# legatus_v0_2.net
KiCad netlist of a schematic drawn in EAGLE
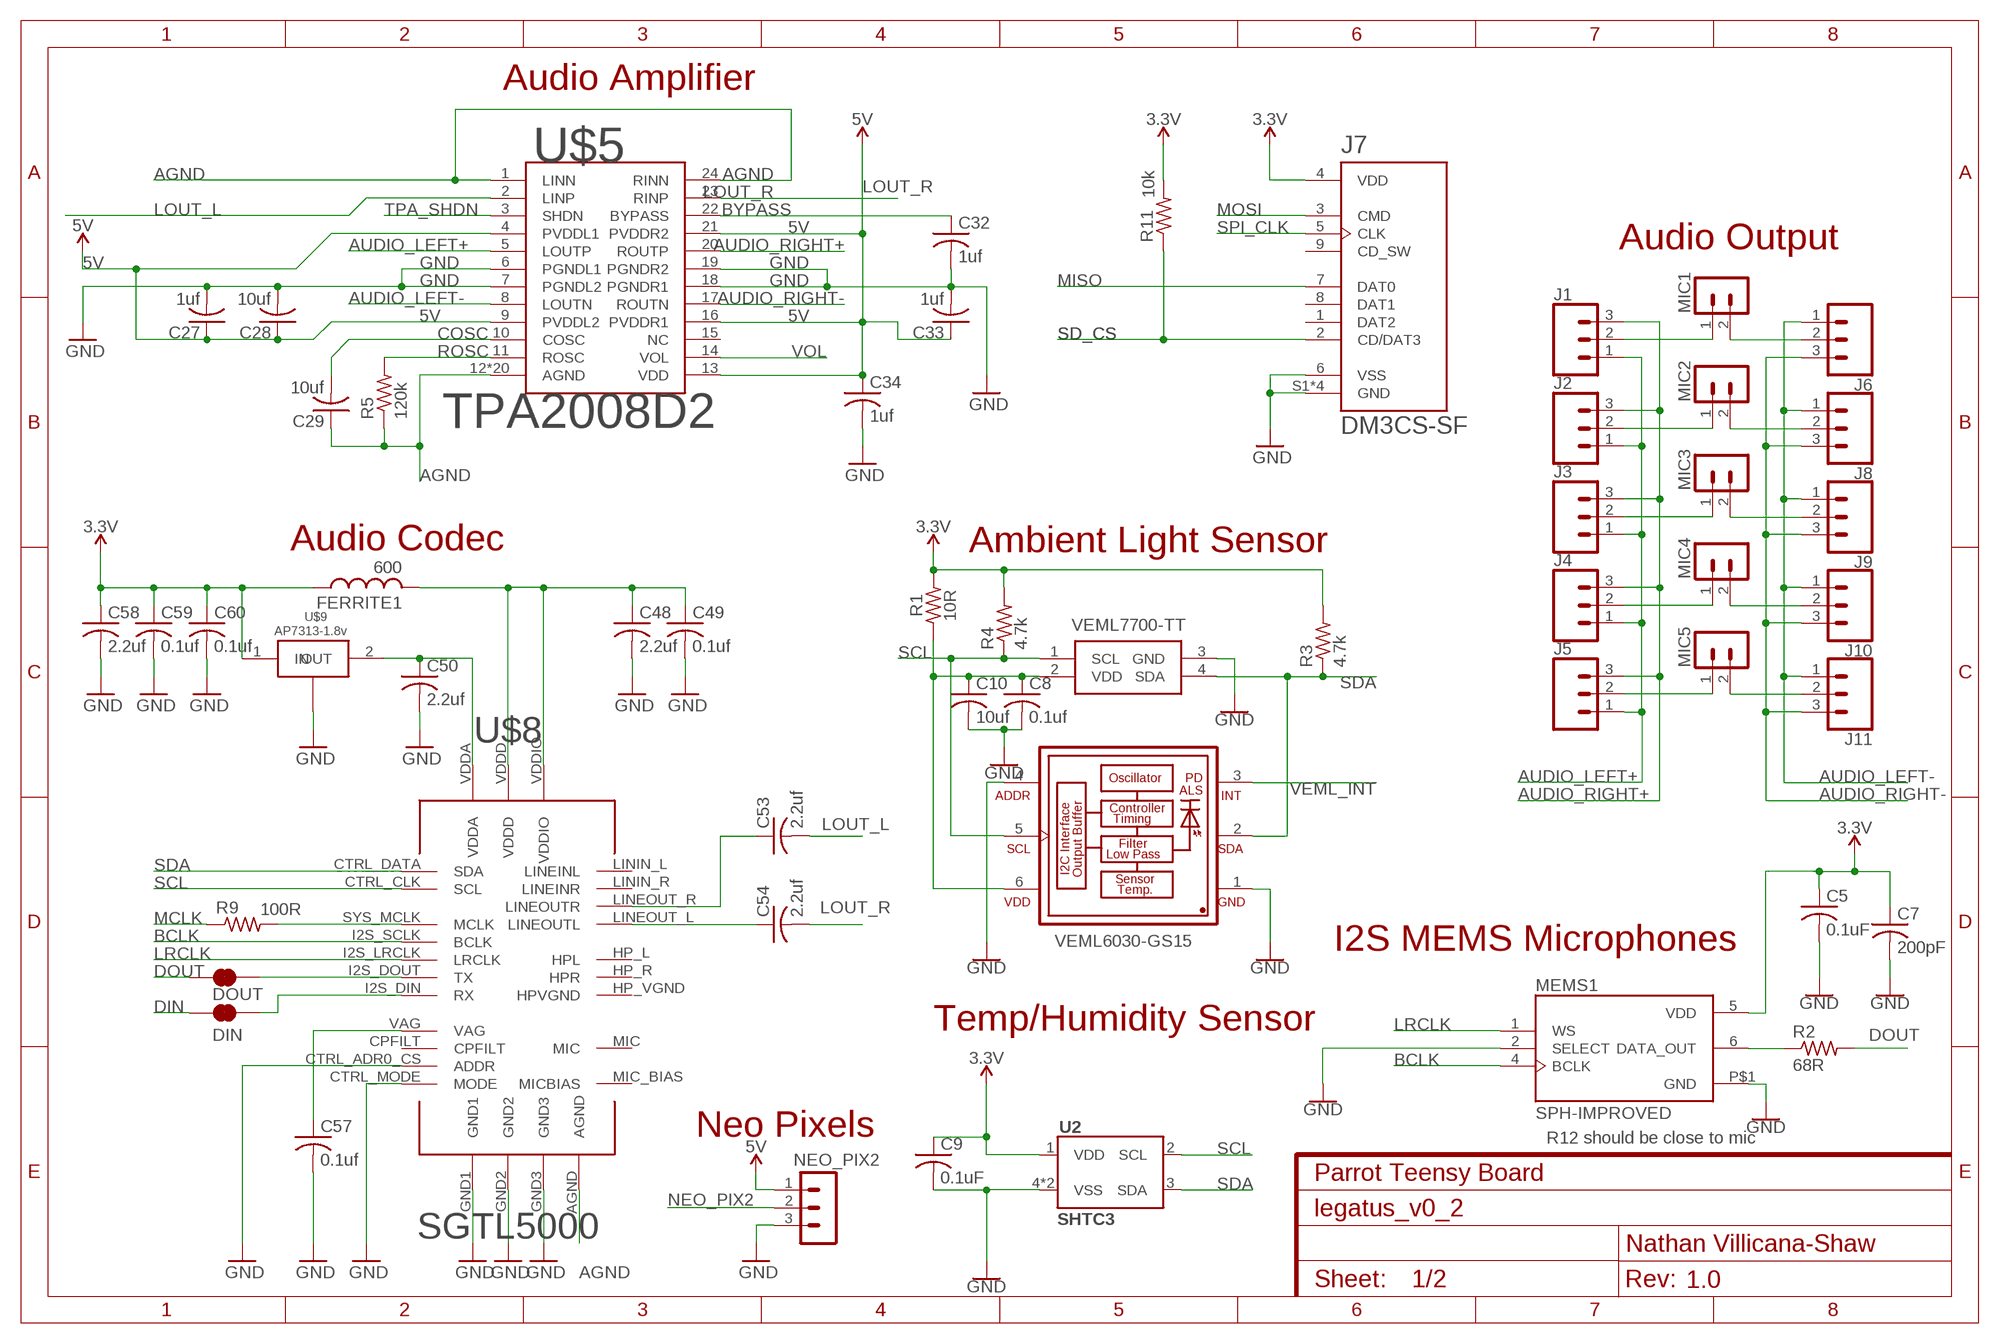
[diagram p0: schematic, sheet 1]
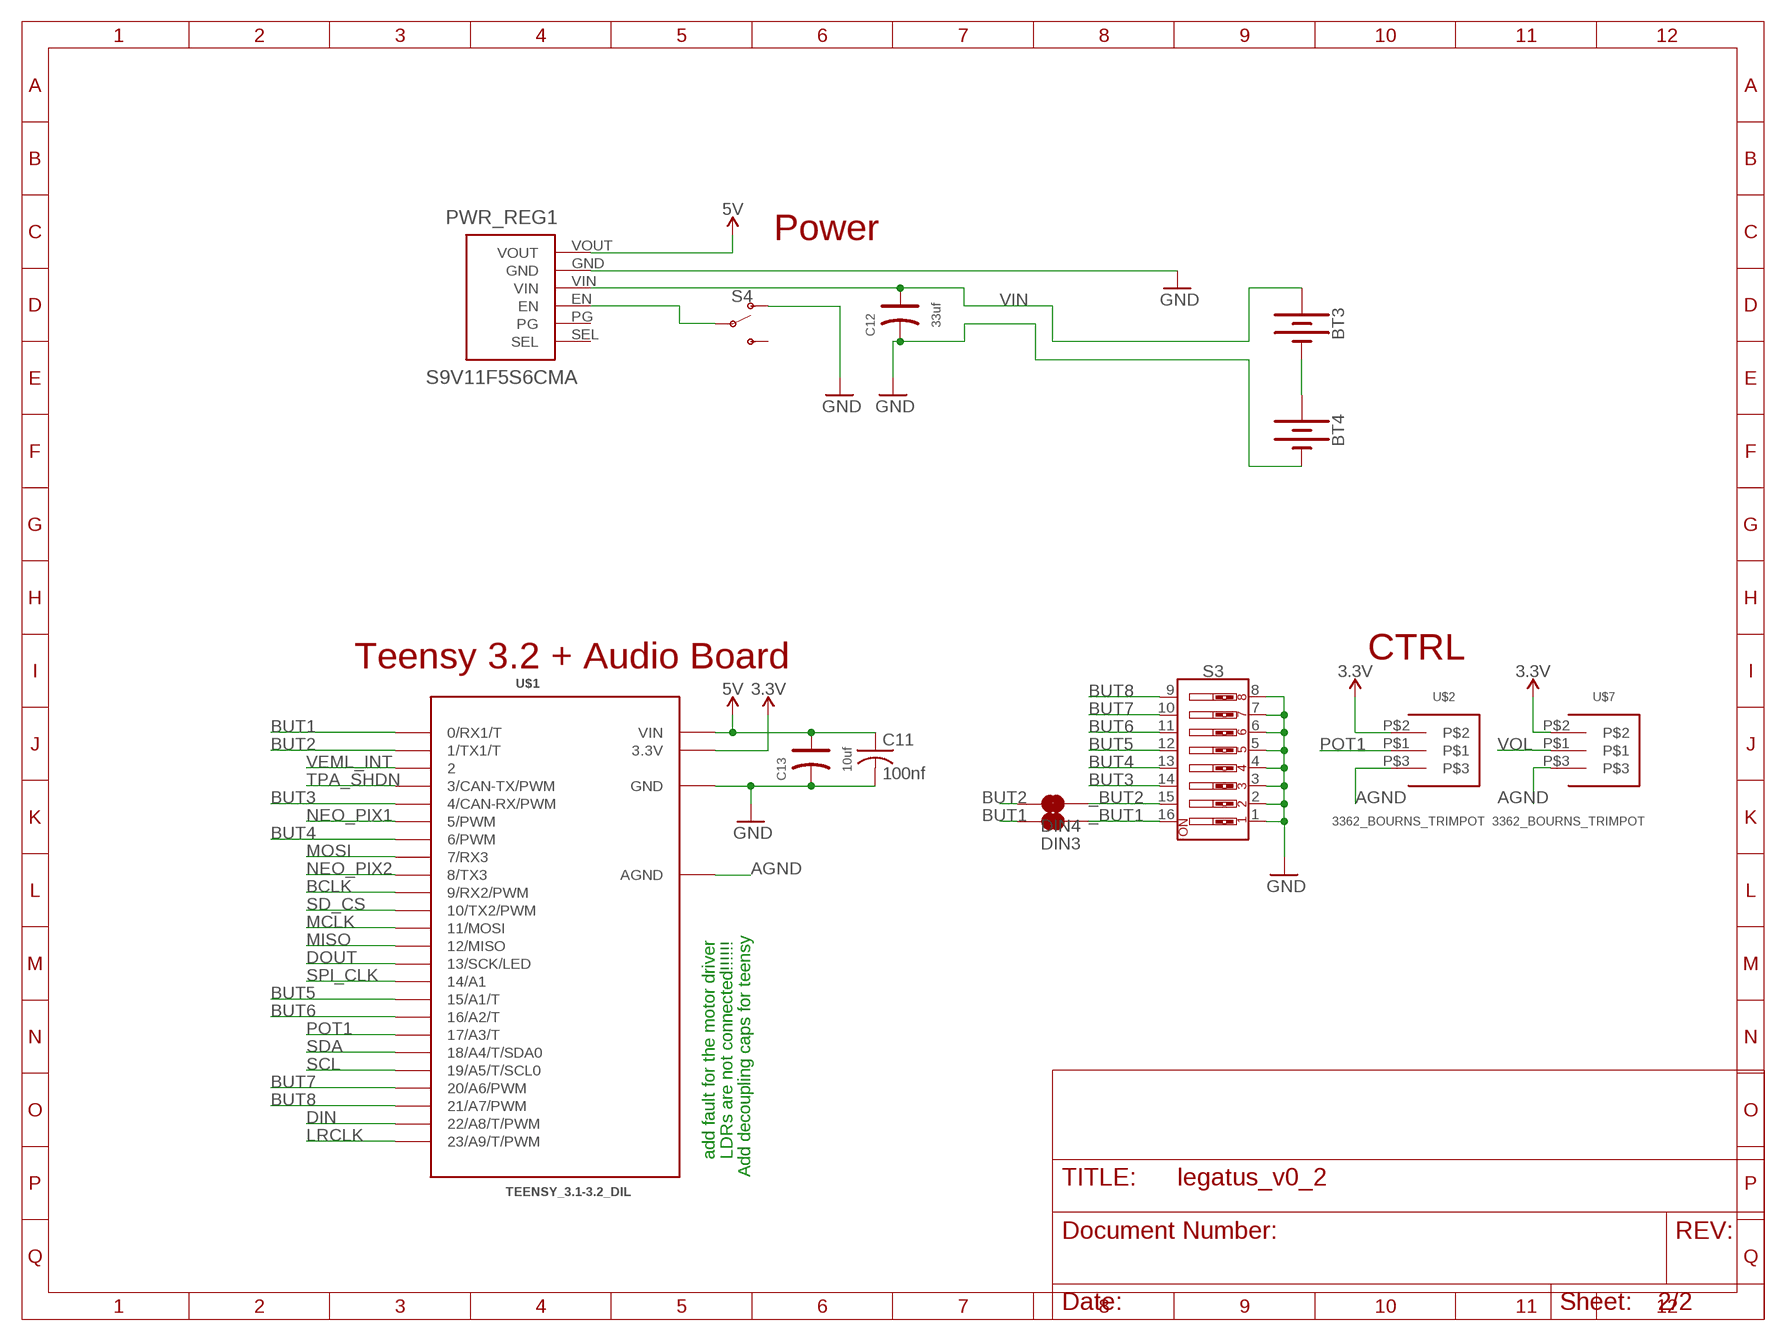
[diagram p1: schematic, sheet 2, part 1 of 2]
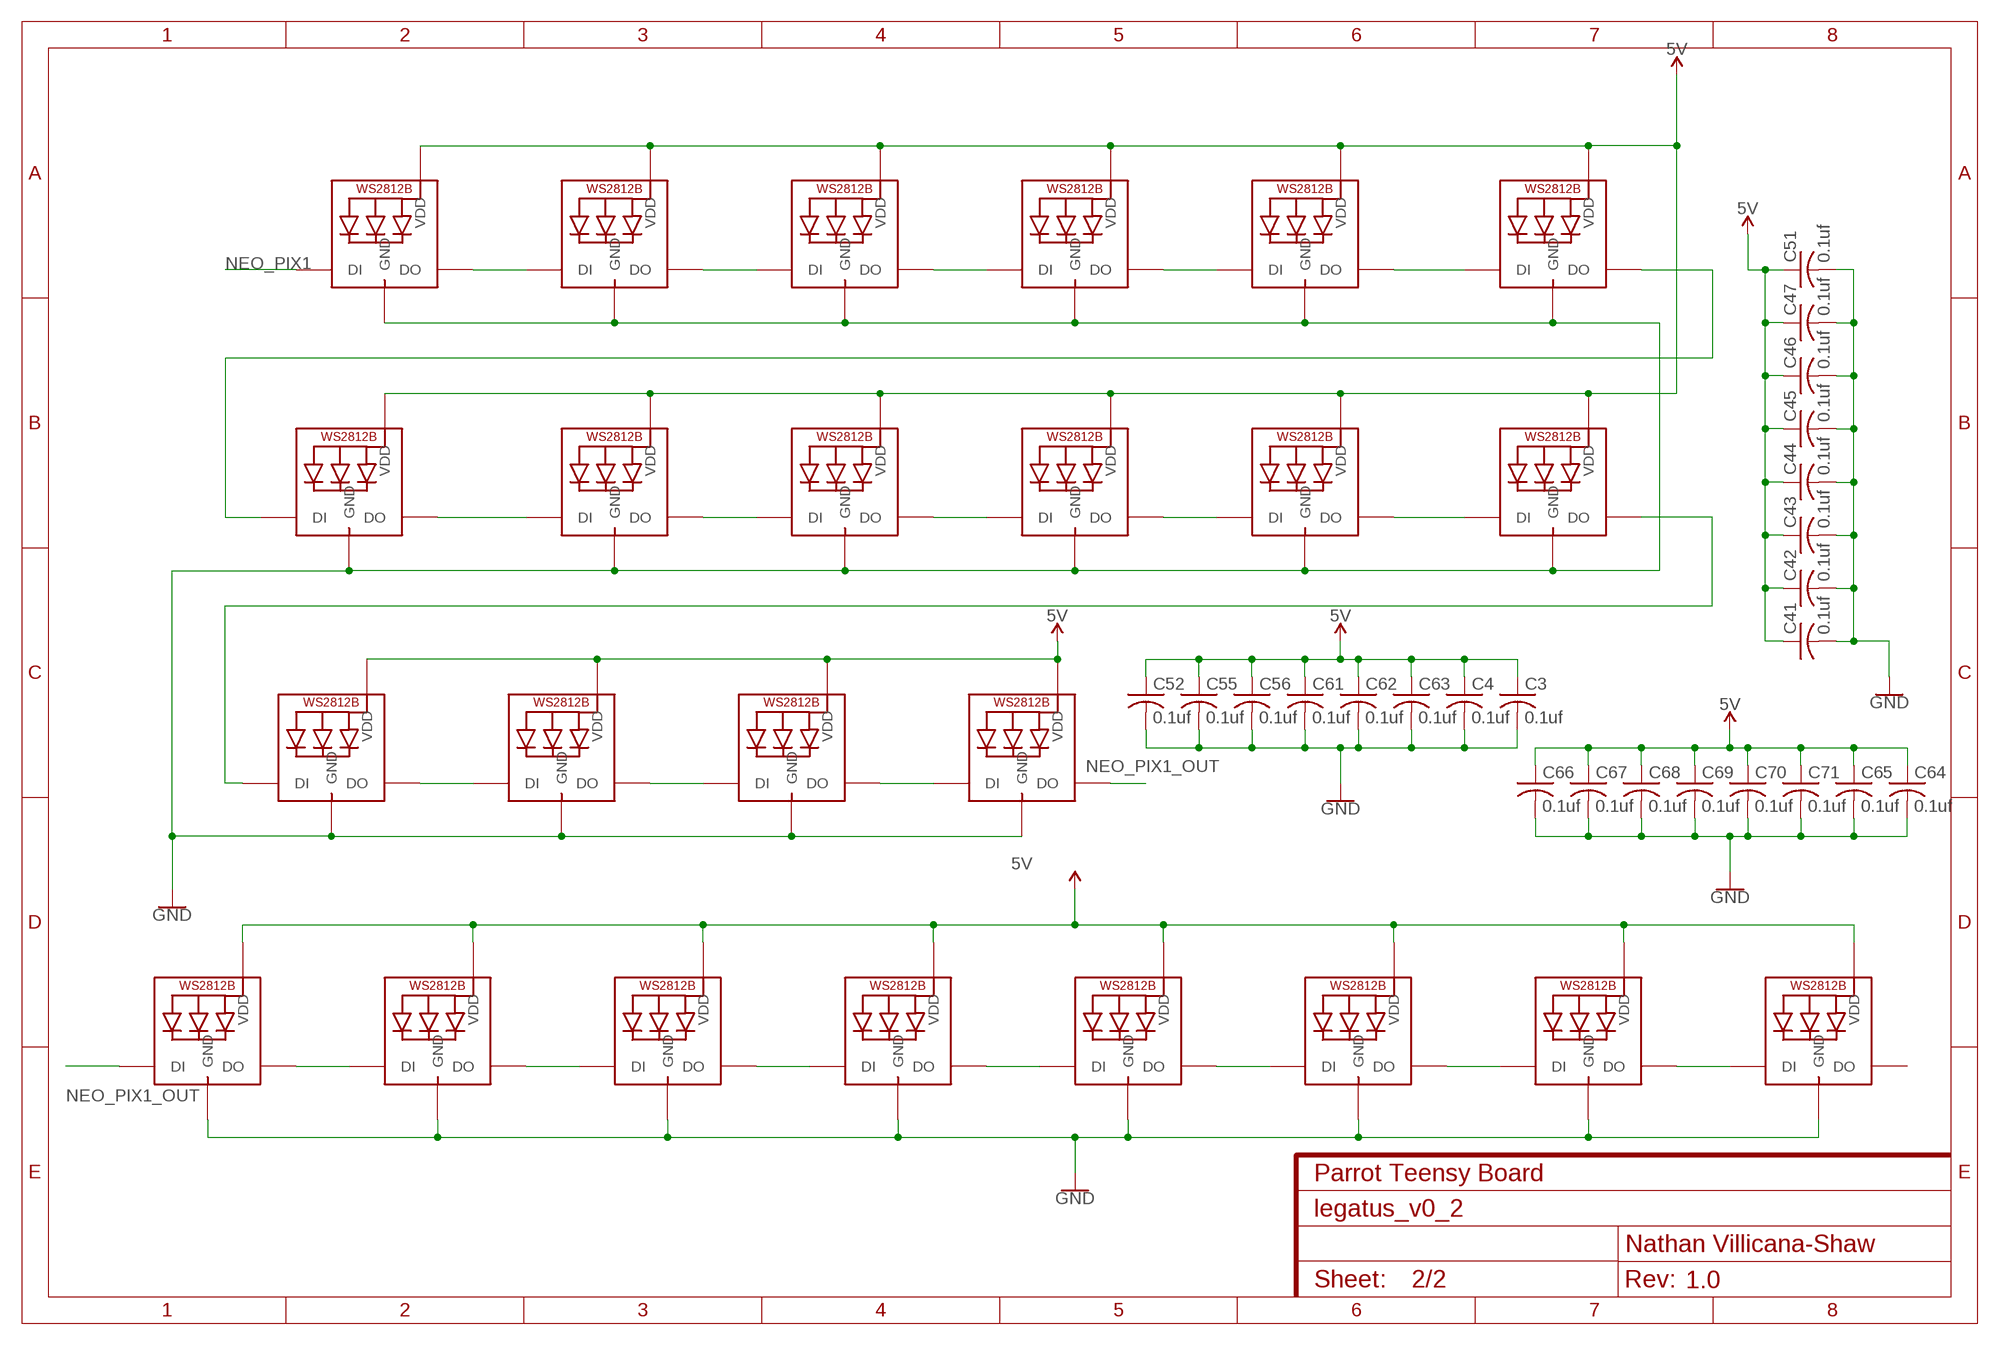
[diagram p2: schematic, sheet 2, part 2 of 2]

(export (version "E")
  (design (tool "Eeschema 10.0.6"))
  (components
    (comp (ref "C5")
      (value "0.1uF")
      (footprint "eagle-import:C0805")
      (libsource (lib "eagle-import") (part "rcl_334_C-USC0805"))
    )
    (comp (ref "C7")
      (value "200pF")
      (footprint "eagle-import:C0805")
      (libsource (lib "eagle-import") (part "rcl_334_C-USC0805"))
    )
    (comp (ref "C8")
      (value "0.1uf")
      (footprint "eagle-import:C0805")
      (libsource (lib "eagle-import") (part "rcl_334_C-USC0805"))
    )
    (comp (ref "C9")
      (value "0.1uF")
      (footprint "eagle-import:C0805")
      (libsource (lib "eagle-import") (part "rcl_334_C-USC0805"))
    )
    (comp (ref "C10")
      (value "10uf")
      (footprint "eagle-import:C0805")
      (libsource (lib "eagle-import") (part "rcl_334_C-USC0805"))
    )
    (comp (ref "C27")
      (value "1uf")
      (footprint "eagle-import:C0805")
      (libsource (lib "eagle-import") (part "rcl_334_C-USC0805"))
    )
    (comp (ref "C28")
      (value "10uf")
      (footprint "eagle-import:C0805")
      (libsource (lib "eagle-import") (part "rcl_334_C-USC0805"))
    )
    (comp (ref "C29")
      (value "10uf")
      (footprint "eagle-import:C0805")
      (libsource (lib "eagle-import") (part "rcl_334_C-USC0805"))
    )
    (comp (ref "C32")
      (value "1uf")
      (footprint "eagle-import:C0805")
      (libsource (lib "eagle-import") (part "rcl_334_C-USC0805"))
    )
    (comp (ref "C33")
      (value "1uf")
      (footprint "eagle-import:C0805")
      (libsource (lib "eagle-import") (part "rcl_334_C-USC0805"))
    )
    (comp (ref "C34")
      (value "1uf")
      (footprint "eagle-import:C0805")
      (libsource (lib "eagle-import") (part "rcl_334_C-USC0805"))
    )
    (comp (ref "C48")
      (value "2.2uf")
      (footprint "eagle-import:C0805")
      (libsource (lib "eagle-import") (part "rcl_334_C-USC0805"))
    )
    (comp (ref "C49")
      (value "0.1uf")
      (footprint "eagle-import:C0805")
      (libsource (lib "eagle-import") (part "rcl_334_C-USC0805"))
    )
    (comp (ref "C50")
      (value "2.2uf")
      (footprint "eagle-import:C0805")
      (libsource (lib "eagle-import") (part "rcl_334_C-USC0805"))
    )
    (comp (ref "C53")
      (value "2.2uf")
      (footprint "eagle-import:C0805")
      (libsource (lib "eagle-import") (part "rcl_334_C-USC0805"))
    )
    (comp (ref "C54")
      (value "2.2uf")
      (footprint "eagle-import:C0805")
      (libsource (lib "eagle-import") (part "rcl_334_C-USC0805"))
    )
    (comp (ref "C57")
      (value "0.1uf")
      (footprint "eagle-import:C0805")
      (libsource (lib "eagle-import") (part "rcl_334_C-USC0805"))
    )
    (comp (ref "C58")
      (value "2.2uf")
      (footprint "eagle-import:C0805")
      (libsource (lib "eagle-import") (part "rcl_334_C-USC0805"))
    )
    (comp (ref "C59")
      (value "0.1uf")
      (footprint "eagle-import:C0805")
      (libsource (lib "eagle-import") (part "rcl_334_C-USC0805"))
    )
    (comp (ref "C60")
      (value "0.1uf")
      (footprint "eagle-import:C0805")
      (libsource (lib "eagle-import") (part "rcl_334_C-USC0805"))
    )
    (comp (ref "DIN")
      (value "JUMPER-SMT_2_NC_TRACE_SILK")
      (footprint "eagle-import:SMT-JUMPER_2_NC_TRACE_SILK")
      (libsource (lib "eagle-import") (part "JUMPER-SMT_2_NC_TRACE_SILK"))
    )
    (comp (ref "DOUT")
      (value "JUMPER-SMT_2_NC_TRACE_SILK")
      (footprint "eagle-import:SMT-JUMPER_2_NC_TRACE_SILK")
      (libsource (lib "eagle-import") (part "JUMPER-SMT_2_NC_TRACE_SILK"))
    )
    (comp (ref "FERRITE1")
      (value "600")
      (footprint "eagle-import:RESC0805_N")
      (libsource (lib "eagle-import") (part "INDUCTOR_0805_N"))
    )
    (comp (ref "J1")
      (value "CONN_03")
      (footprint "eagle-import:1X03")
      (libsource (lib "eagle-import") (part "CONN_03"))
    )
    (comp (ref "J2")
      (value "CONN_03")
      (footprint "eagle-import:1X03")
      (libsource (lib "eagle-import") (part "CONN_03"))
    )
    (comp (ref "J3")
      (value "CONN_03")
      (footprint "eagle-import:1X03")
      (libsource (lib "eagle-import") (part "CONN_03"))
    )
    (comp (ref "J4")
      (value "CONN_03")
      (footprint "eagle-import:1X03")
      (libsource (lib "eagle-import") (part "CONN_03"))
    )
    (comp (ref "J5")
      (value "CONN_03")
      (footprint "eagle-import:1X03")
      (libsource (lib "eagle-import") (part "CONN_03"))
    )
    (comp (ref "J6")
      (value "CONN_03")
      (footprint "eagle-import:1X03")
      (libsource (lib "eagle-import") (part "CONN_03"))
    )
    (comp (ref "J7")
      (value "DM3CS-SF")
      (footprint "eagle-import:HRS_DM3CS-SF")
      (fields (field (name "MF") "Hirose"))
      (libsource (lib "eagle-import") (part "DM3CS-SF"))
    )
    (comp (ref "J8")
      (value "CONN_03")
      (footprint "eagle-import:1X03")
      (libsource (lib "eagle-import") (part "CONN_03"))
    )
    (comp (ref "J9")
      (value "CONN_03")
      (footprint "eagle-import:1X03")
      (libsource (lib "eagle-import") (part "CONN_03"))
    )
    (comp (ref "J10")
      (value "CONN_03")
      (footprint "eagle-import:1X03")
      (libsource (lib "eagle-import") (part "CONN_03"))
    )
    (comp (ref "J11")
      (value "CONN_03")
      (footprint "eagle-import:1X03")
      (libsource (lib "eagle-import") (part "CONN_03"))
    )
    (comp (ref "MEMS1")
      (value "SPH-IMPROVED")
      (footprint "eagle-import:MIC_SPH0645LM4H-B_LARGER_RING")
      (libsource (lib "eagle-import") (part "SPH-IMPROVED"))
    )
    (comp (ref "MIC1")
      (value "B2B-PH-K")
      (footprint "eagle-import:B2B-PH-K")
      (libsource (lib "eagle-import") (part "B2B-PH-K"))
    )
    (comp (ref "MIC2")
      (value "B2B-PH-K")
      (footprint "eagle-import:B2B-PH-K")
      (libsource (lib "eagle-import") (part "B2B-PH-K"))
    )
    (comp (ref "MIC3")
      (value "B2B-PH-K")
      (footprint "eagle-import:B2B-PH-K")
      (libsource (lib "eagle-import") (part "B2B-PH-K"))
    )
    (comp (ref "MIC4")
      (value "B2B-PH-K")
      (footprint "eagle-import:B2B-PH-K")
      (libsource (lib "eagle-import") (part "B2B-PH-K"))
    )
    (comp (ref "MIC5")
      (value "B2B-PH-K")
      (footprint "eagle-import:B2B-PH-K")
      (libsource (lib "eagle-import") (part "B2B-PH-K"))
    )
    (comp (ref "NEO_PIX2")
      (value "B3B-PH-K")
      (footprint "eagle-import:B3B-PH-K")
      (libsource (lib "eagle-import") (part "B3B-PH-K"))
    )
    (comp (ref "R1")
      (value "10R")
      (footprint "eagle-import:R0805")
      (libsource (lib "eagle-import") (part "audio amplifier example_970892_R-US_R0805"))
    )
    (comp (ref "R2")
      (value "68R")
      (footprint "eagle-import:M0805")
      (libsource (lib "eagle-import") (part "R-US_M0805"))
    )
    (comp (ref "R3")
      (value "4.7k")
      (footprint "eagle-import:M0805")
      (libsource (lib "eagle-import") (part "R-US_M0805"))
    )
    (comp (ref "R4")
      (value "4.7k")
      (footprint "eagle-import:M0805")
      (libsource (lib "eagle-import") (part "R-US_M0805"))
    )
    (comp (ref "R5")
      (value "120k")
      (footprint "eagle-import:M0805")
      (libsource (lib "eagle-import") (part "R-US_M0805"))
    )
    (comp (ref "R9")
      (value "100R")
      (footprint "eagle-import:M0805")
      (libsource (lib "eagle-import") (part "rcl_R-US_M0805"))
    )
    (comp (ref "R11")
      (value "10k")
      (footprint "eagle-import:M0805")
      (libsource (lib "eagle-import") (part "rcl_R-US_M0805"))
    )
    (comp (ref "U$5")
      (value "TPA2008D2")
      (footprint "eagle-import:PWP-TSSOP24")
      (libsource (lib "eagle-import") (part "TPA2008D2"))
    )
    (comp (ref "U$8")
      (value "SGTL5000")
      (footprint "eagle-import:QFN-32-5X5MM")
      (libsource (lib "eagle-import") (part "SGTL5000"))
    )
    (comp (ref "U$9")
      (value "AP7313-1.8v")
      (footprint "eagle-import:SOT-23")
      (libsource (lib "eagle-import") (part "AP7313"))
    )
    (comp (ref "U2")
      (value "SHTC3")
      (footprint "eagle-import:SHTC3")
      (libsource (lib "eagle-import") (part "SHTC3"))
    )
    (comp (ref "VEML1")
      (value "VEML7700-TT")
      (footprint "eagle-import:VEML7700")
      (fields (field (name "MOUSER_PART_NUMBER") "78-VEML7700-TT") (field (name "RS_PART_NUMBER") "1226791P"))
      (libsource (lib "eagle-import") (part "VEML7700-TT"))
    )
    (comp (ref "VMEL1")
      (value "VEML6030-GS15")
      (footprint "eagle-import:VISHAY_VEML6030_2X2X0.87")
      (fields (field (name "MF") "Vishay Semiconductor"))
      (libsource (lib "eagle-import") (part "VEML6030-GS15"))
    )
    (comp (ref "BT3")
      (value "BATTERY-18650")
      (footprint "eagle-import:BATTERY_18650-HOLDER")
      (libsource (lib "eagle-import") (part "BATTERY-18650"))
    )
    (comp (ref "BT4")
      (value "BATTERY-18650")
      (footprint "eagle-import:BATTERY_18650-HOLDER")
      (libsource (lib "eagle-import") (part "BATTERY-18650"))
    )
    (comp (ref "C3")
      (value "0.1uf")
      (footprint "eagle-import:C0805")
      (libsource (lib "eagle-import") (part "rcl_334_C-USC0805"))
    )
    (comp (ref "C4")
      (value "0.1uf")
      (footprint "eagle-import:C0805")
      (libsource (lib "eagle-import") (part "rcl_334_C-USC0805"))
    )
    (comp (ref "C11")
      (value "100nf")
      (footprint "eagle-import:C2012")
      (libsource (lib "eagle-import") (part "C-USC2012"))
    )
    (comp (ref "C12")
      (value "33uf")
      (footprint "eagle-import:PC-D5.3MM")
      (fields (field (name "MPN") "KS 100uF/16V"))
      (libsource (lib "eagle-import") (part "DIP-ALUMINUM-47UF-16V(D5-H7MM)"))
    )
    (comp (ref "C13")
      (value "10uf")
      (footprint "eagle-import:PC-D5.3MM")
      (fields (field (name "MPN") "KS 100uF/16V"))
      (libsource (lib "eagle-import") (part "DIP-ALUMINUM-47UF-16V(D5-H7MM)"))
    )
    (comp (ref "C41")
      (value "0.1uf")
      (footprint "eagle-import:C0805")
      (libsource (lib "eagle-import") (part "rcl_334_C-USC0805"))
    )
    (comp (ref "C42")
      (value "0.1uf")
      (footprint "eagle-import:C0805")
      (libsource (lib "eagle-import") (part "rcl_334_C-USC0805"))
    )
    (comp (ref "C43")
      (value "0.1uf")
      (footprint "eagle-import:C0805")
      (libsource (lib "eagle-import") (part "rcl_334_C-USC0805"))
    )
    (comp (ref "C44")
      (value "0.1uf")
      (footprint "eagle-import:C0805")
      (libsource (lib "eagle-import") (part "rcl_334_C-USC0805"))
    )
    (comp (ref "C45")
      (value "0.1uf")
      (footprint "eagle-import:C0805")
      (libsource (lib "eagle-import") (part "rcl_334_C-USC0805"))
    )
    (comp (ref "C46")
      (value "0.1uf")
      (footprint "eagle-import:C0805")
      (libsource (lib "eagle-import") (part "rcl_334_C-USC0805"))
    )
    (comp (ref "C47")
      (value "0.1uf")
      (footprint "eagle-import:C0805")
      (libsource (lib "eagle-import") (part "rcl_334_C-USC0805"))
    )
    (comp (ref "C51")
      (value "0.1uf")
      (footprint "eagle-import:C0805")
      (libsource (lib "eagle-import") (part "rcl_334_C-USC0805"))
    )
    (comp (ref "C52")
      (value "0.1uf")
      (footprint "eagle-import:C0805")
      (libsource (lib "eagle-import") (part "rcl_334_C-USC0805"))
    )
    (comp (ref "C55")
      (value "0.1uf")
      (footprint "eagle-import:C0805")
      (libsource (lib "eagle-import") (part "rcl_334_C-USC0805"))
    )
    (comp (ref "C56")
      (value "0.1uf")
      (footprint "eagle-import:C0805")
      (libsource (lib "eagle-import") (part "rcl_334_C-USC0805"))
    )
    (comp (ref "C61")
      (value "0.1uf")
      (footprint "eagle-import:C0805")
      (libsource (lib "eagle-import") (part "rcl_334_C-USC0805"))
    )
    (comp (ref "C62")
      (value "0.1uf")
      (footprint "eagle-import:C0805")
      (libsource (lib "eagle-import") (part "rcl_334_C-USC0805"))
    )
    (comp (ref "C63")
      (value "0.1uf")
      (footprint "eagle-import:C0805")
      (libsource (lib "eagle-import") (part "rcl_334_C-USC0805"))
    )
    (comp (ref "C64")
      (value "0.1uf")
      (footprint "eagle-import:C0805")
      (libsource (lib "eagle-import") (part "rcl_334_C-USC0805"))
    )
    (comp (ref "C65")
      (value "0.1uf")
      (footprint "eagle-import:C0805")
      (libsource (lib "eagle-import") (part "rcl_334_C-USC0805"))
    )
    (comp (ref "C66")
      (value "0.1uf")
      (footprint "eagle-import:C0805")
      (libsource (lib "eagle-import") (part "rcl_334_C-USC0805"))
    )
    (comp (ref "C67")
      (value "0.1uf")
      (footprint "eagle-import:C0805")
      (libsource (lib "eagle-import") (part "rcl_334_C-USC0805"))
    )
    (comp (ref "C68")
      (value "0.1uf")
      (footprint "eagle-import:C0805")
      (libsource (lib "eagle-import") (part "rcl_334_C-USC0805"))
    )
    (comp (ref "C69")
      (value "0.1uf")
      (footprint "eagle-import:C0805")
      (libsource (lib "eagle-import") (part "rcl_334_C-USC0805"))
    )
    (comp (ref "C70")
      (value "0.1uf")
      (footprint "eagle-import:C0805")
      (libsource (lib "eagle-import") (part "rcl_334_C-USC0805"))
    )
    (comp (ref "C71")
      (value "0.1uf")
      (footprint "eagle-import:C0805")
      (libsource (lib "eagle-import") (part "rcl_334_C-USC0805"))
    )
    (comp (ref "DIN3")
      (value "JUMPER-SMT_2_NC_TRACE_SILK")
      (footprint "eagle-import:SMT-JUMPER_2_NC_TRACE_SILK")
      (libsource (lib "eagle-import") (part "JUMPER-SMT_2_NC_TRACE_SILK"))
    )
    (comp (ref "DIN4")
      (value "JUMPER-SMT_2_NC_TRACE_SILK")
      (footprint "eagle-import:SMT-JUMPER_2_NC_TRACE_SILK")
      (libsource (lib "eagle-import") (part "JUMPER-SMT_2_NC_TRACE_SILK"))
    )
    (comp (ref "LED25")
      (value "WS2812B_5050N")
      (footprint "eagle-import:WS2812B-NARROW")
      (libsource (lib "eagle-import") (part "WS2812B_5050N"))
    )
    (comp (ref "LED26")
      (value "WS2812B_5050N")
      (footprint "eagle-import:WS2812B-NARROW")
      (libsource (lib "eagle-import") (part "WS2812B_5050N"))
    )
    (comp (ref "LED27")
      (value "WS2812B_5050N")
      (footprint "eagle-import:WS2812B-NARROW")
      (libsource (lib "eagle-import") (part "WS2812B_5050N"))
    )
    (comp (ref "LED28")
      (value "WS2812B_5050N")
      (footprint "eagle-import:WS2812B-NARROW")
      (libsource (lib "eagle-import") (part "WS2812B_5050N"))
    )
    (comp (ref "LED29")
      (value "WS2812B_5050N")
      (footprint "eagle-import:WS2812B-NARROW")
      (libsource (lib "eagle-import") (part "WS2812B_5050N"))
    )
    (comp (ref "LED30")
      (value "WS2812B_5050N")
      (footprint "eagle-import:WS2812B-NARROW")
      (libsource (lib "eagle-import") (part "WS2812B_5050N"))
    )
    (comp (ref "LED31")
      (value "WS2812B_5050N")
      (footprint "eagle-import:WS2812B-NARROW")
      (libsource (lib "eagle-import") (part "WS2812B_5050N"))
    )
    (comp (ref "LED32")
      (value "WS2812B_5050N")
      (footprint "eagle-import:WS2812B-NARROW")
      (libsource (lib "eagle-import") (part "WS2812B_5050N"))
    )
    (comp (ref "LED33")
      (value "WS2812B_5050N")
      (footprint "eagle-import:WS2812B-NARROW")
      (libsource (lib "eagle-import") (part "WS2812B_5050N"))
    )
    (comp (ref "LED34")
      (value "WS2812B_5050N")
      (footprint "eagle-import:WS2812B-NARROW")
      (libsource (lib "eagle-import") (part "WS2812B_5050N"))
    )
    (comp (ref "LED35")
      (value "WS2812B_5050N")
      (footprint "eagle-import:WS2812B-NARROW")
      (libsource (lib "eagle-import") (part "WS2812B_5050N"))
    )
    (comp (ref "LED36")
      (value "WS2812B_5050N")
      (footprint "eagle-import:WS2812B-NARROW")
      (libsource (lib "eagle-import") (part "WS2812B_5050N"))
    )
    (comp (ref "LED37")
      (value "WS2812B_5050N")
      (footprint "eagle-import:WS2812B-NARROW")
      (libsource (lib "eagle-import") (part "WS2812B_5050N"))
    )
    (comp (ref "LED38")
      (value "WS2812B_5050N")
      (footprint "eagle-import:WS2812B-NARROW")
      (libsource (lib "eagle-import") (part "WS2812B_5050N"))
    )
    (comp (ref "LED39")
      (value "WS2812B_5050N")
      (footprint "eagle-import:WS2812B-NARROW")
      (libsource (lib "eagle-import") (part "WS2812B_5050N"))
    )
    (comp (ref "LED40")
      (value "WS2812B_5050N")
      (footprint "eagle-import:WS2812B-NARROW")
      (libsource (lib "eagle-import") (part "WS2812B_5050N"))
    )
    (comp (ref "LED41")
      (value "WS2812B_5050N")
      (footprint "eagle-import:WS2812B-NARROW")
      (libsource (lib "eagle-import") (part "WS2812B_5050N"))
    )
    (comp (ref "LED42")
      (value "WS2812B_5050N")
      (footprint "eagle-import:WS2812B-NARROW")
      (libsource (lib "eagle-import") (part "WS2812B_5050N"))
    )
    (comp (ref "LED43")
      (value "WS2812B_5050N")
      (footprint "eagle-import:WS2812B-NARROW")
      (libsource (lib "eagle-import") (part "WS2812B_5050N"))
    )
    (comp (ref "LED44")
      (value "WS2812B_5050N")
      (footprint "eagle-import:WS2812B-NARROW")
      (libsource (lib "eagle-import") (part "WS2812B_5050N"))
    )
    (comp (ref "LED45")
      (value "WS2812B_5050N")
      (footprint "eagle-import:WS2812B-NARROW")
      (libsource (lib "eagle-import") (part "WS2812B_5050N"))
    )
    (comp (ref "LED46")
      (value "WS2812B_5050N")
      (footprint "eagle-import:WS2812B-NARROW")
      (libsource (lib "eagle-import") (part "WS2812B_5050N"))
    )
    (comp (ref "LED47")
      (value "WS2812B_5050N")
      (footprint "eagle-import:WS2812B-NARROW")
      (libsource (lib "eagle-import") (part "WS2812B_5050N"))
    )
    (comp (ref "LED48")
      (value "WS2812B_5050N")
      (footprint "eagle-import:WS2812B-NARROW")
      (libsource (lib "eagle-import") (part "WS2812B_5050N"))
    )
    (comp (ref "PWR_REG1")
      (value "S9V11F5S6CMA")
      (footprint "eagle-import:S9V11F3S5CMA")
      (libsource (lib "eagle-import") (part "S9V11F5S6CMA"))
    )
    (comp (ref "S3")
      (value "DIP-08-PTH")
      (footprint "eagle-import:DIPSWITCH-08")
      (libsource (lib "eagle-import") (part "DIP-08-PTH"))
    )
    (comp (ref "S4")
      (value "SWITCH-SPDT-PTH-11.6X4.0MM-LOCK")
      (footprint "eagle-import:SWITCH_SPDT_PTH_11.6X4.0MM_LOCK")
      (libsource (lib "eagle-import") (part "SWITCH-SPDT-PTH-11.6X4.0MM-LOCK"))
    )
    (comp (ref "U$1")
      (value "TEENSY_3.1-3.2_DIL")
      (footprint "eagle-import:TEENSY_3.0-3.2&LC_DIL")
      (libsource (lib "eagle-import") (part "TEENSY_3.1-3.2_DIL"))
    )
    (comp (ref "U$2")
      (value "3362_BOURNS_TRIMPOT")
      (footprint "eagle-import:3362_BOURNS_TRIMPOT")
      (libsource (lib "eagle-import") (part "3362_BOURNS_TRIMPOT"))
    )
    (comp (ref "U$7")
      (value "3362_BOURNS_TRIMPOT")
      (footprint "eagle-import:3362_BOURNS_TRIMPOT")
      (libsource (lib "eagle-import") (part "3362_BOURNS_TRIMPOT"))
    )
  )
  (nets
    (net (code "1") (name "3.3V") (class "Default")
      (node (ref "C5") (pin "1") (pinfunction "1_1") (pintype "passive"))
      (node (ref "C58") (pin "1") (pinfunction "1_1") (pintype "passive"))
      (node (ref "C59") (pin "1") (pinfunction "1_1") (pintype "passive"))
      (node (ref "C60") (pin "1") (pinfunction "1_1") (pintype "passive"))
      (node (ref "C7") (pin "1") (pinfunction "1_1") (pintype "passive"))
      (node (ref "C9") (pin "1") (pinfunction "1_1") (pintype "passive"))
      (node (ref "FERRITE1") (pin "1") (pinfunction "1_1") (pintype "passive"))
      (node (ref "J7") (pin "4") (pinfunction "VDD_4") (pintype "passive"))
      (node (ref "MEMS1") (pin "5") (pinfunction "VDD_5") (pintype "power_in"))
      (node (ref "R1") (pin "2") (pinfunction "2_2") (pintype "passive"))
      (node (ref "R11") (pin "2") (pinfunction "2_2") (pintype "passive"))
      (node (ref "R3") (pin "2") (pinfunction "2_2") (pintype "passive"))
      (node (ref "R4") (pin "2") (pinfunction "2_2") (pintype "passive"))
      (node (ref "U$1") (pin "3.3V") (pinfunction "3.3V_3.3V") (pintype "power_in"))
      (node (ref "U$2") (pin "P$2") (pinfunction "P$2_P$2") (pintype "bidirectional"))
      (node (ref "U$7") (pin "P$2") (pinfunction "P$2_P$2") (pintype "bidirectional"))
      (node (ref "U$9") (pin "1") (pinfunction "IN_1") (pintype "bidirectional"))
      (node (ref "U2") (pin "1") (pinfunction "VDD_1") (pintype "bidirectional"))
    )
    (net (code "2") (name "5V") (class "Default")
      (node (ref "C11") (pin "1") (pinfunction "1_1") (pintype "passive"))
      (node (ref "C13") (pin "+") (pinfunction "+_+") (pintype "passive"))
      (node (ref "C27") (pin "1") (pinfunction "1_1") (pintype "passive"))
      (node (ref "C28") (pin "1") (pinfunction "1_1") (pintype "passive"))
      (node (ref "C3") (pin "1") (pinfunction "1_1") (pintype "passive"))
      (node (ref "C33") (pin "1") (pinfunction "1_1") (pintype "passive"))
      (node (ref "C34") (pin "1") (pinfunction "1_1") (pintype "passive"))
      (node (ref "C4") (pin "1") (pinfunction "1_1") (pintype "passive"))
      (node (ref "C41") (pin "1") (pinfunction "1_1") (pintype "passive"))
      (node (ref "C42") (pin "1") (pinfunction "1_1") (pintype "passive"))
      (node (ref "C43") (pin "1") (pinfunction "1_1") (pintype "passive"))
      (node (ref "C44") (pin "1") (pinfunction "1_1") (pintype "passive"))
      (node (ref "C45") (pin "1") (pinfunction "1_1") (pintype "passive"))
      (node (ref "C46") (pin "1") (pinfunction "1_1") (pintype "passive"))
      (node (ref "C47") (pin "1") (pinfunction "1_1") (pintype "passive"))
      (node (ref "C51") (pin "1") (pinfunction "1_1") (pintype "passive"))
      (node (ref "C52") (pin "1") (pinfunction "1_1") (pintype "passive"))
      (node (ref "C55") (pin "1") (pinfunction "1_1") (pintype "passive"))
      (node (ref "C56") (pin "1") (pinfunction "1_1") (pintype "passive"))
      (node (ref "C61") (pin "1") (pinfunction "1_1") (pintype "passive"))
      (node (ref "C62") (pin "1") (pinfunction "1_1") (pintype "passive"))
      (node (ref "C63") (pin "1") (pinfunction "1_1") (pintype "passive"))
      (node (ref "C64") (pin "1") (pinfunction "1_1") (pintype "passive"))
      (node (ref "C65") (pin "1") (pinfunction "1_1") (pintype "passive"))
      (node (ref "C66") (pin "1") (pinfunction "1_1") (pintype "passive"))
      (node (ref "C67") (pin "1") (pinfunction "1_1") (pintype "passive"))
      (node (ref "C68") (pin "1") (pinfunction "1_1") (pintype "passive"))
      (node (ref "C69") (pin "1") (pinfunction "1_1") (pintype "passive"))
      (node (ref "C70") (pin "1") (pinfunction "1_1") (pintype "passive"))
      (node (ref "C71") (pin "1") (pinfunction "1_1") (pintype "passive"))
      (node (ref "LED25") (pin "1-VDD") (pinfunction "VDD_1-VDD") (pintype "power_in"))
      (node (ref "LED26") (pin "1-VDD") (pinfunction "VDD_1-VDD") (pintype "power_in"))
      (node (ref "LED27") (pin "1-VDD") (pinfunction "VDD_1-VDD") (pintype "power_in"))
      (node (ref "LED28") (pin "1-VDD") (pinfunction "VDD_1-VDD") (pintype "power_in"))
      (node (ref "LED29") (pin "1-VDD") (pinfunction "VDD_1-VDD") (pintype "power_in"))
      (node (ref "LED30") (pin "1-VDD") (pinfunction "VDD_1-VDD") (pintype "power_in"))
      (node (ref "LED31") (pin "1-VDD") (pinfunction "VDD_1-VDD") (pintype "power_in"))
      (node (ref "LED32") (pin "1-VDD") (pinfunction "VDD_1-VDD") (pintype "power_in"))
      (node (ref "LED33") (pin "1-VDD") (pinfunction "VDD_1-VDD") (pintype "power_in"))
      (node (ref "LED34") (pin "1-VDD") (pinfunction "VDD_1-VDD") (pintype "power_in"))
      (node (ref "LED35") (pin "1-VDD") (pinfunction "VDD_1-VDD") (pintype "power_in"))
      (node (ref "LED36") (pin "1-VDD") (pinfunction "VDD_1-VDD") (pintype "power_in"))
      (node (ref "LED37") (pin "1-VDD") (pinfunction "VDD_1-VDD") (pintype "power_in"))
      (node (ref "LED38") (pin "1-VDD") (pinfunction "VDD_1-VDD") (pintype "power_in"))
      (node (ref "LED39") (pin "1-VDD") (pinfunction "VDD_1-VDD") (pintype "power_in"))
      (node (ref "LED40") (pin "1-VDD") (pinfunction "VDD_1-VDD") (pintype "power_in"))
      (node (ref "LED41") (pin "1-VDD") (pinfunction "VDD_1-VDD") (pintype "power_in"))
      (node (ref "LED42") (pin "1-VDD") (pinfunction "VDD_1-VDD") (pintype "power_in"))
      (node (ref "LED43") (pin "1-VDD") (pinfunction "VDD_1-VDD") (pintype "power_in"))
      (node (ref "LED44") (pin "1-VDD") (pinfunction "VDD_1-VDD") (pintype "power_in"))
      (node (ref "LED45") (pin "1-VDD") (pinfunction "VDD_1-VDD") (pintype "power_in"))
      (node (ref "LED46") (pin "1-VDD") (pinfunction "VDD_1-VDD") (pintype "power_in"))
      (node (ref "LED47") (pin "1-VDD") (pinfunction "VDD_1-VDD") (pintype "power_in"))
      (node (ref "LED48") (pin "1-VDD") (pinfunction "VDD_1-VDD") (pintype "power_in"))
      (node (ref "NEO_PIX2") (pin "1") (pinfunction "1_1") (pintype "passive"))
      (node (ref "PWR_REG1") (pin "VOUT") (pinfunction "VOUT_VOUT") (pintype "bidirectional"))
      (node (ref "U$1") (pin "VIN") (pinfunction "VIN_VIN") (pintype "power_in"))
      (node (ref "U$5") (pin "13") (pinfunction "VDD_13") (pintype "bidirectional"))
      (node (ref "U$5") (pin "16") (pinfunction "PVDDR1_16") (pintype "bidirectional"))
      (node (ref "U$5") (pin "21") (pinfunction "PVDDR2_21") (pintype "bidirectional"))
      (node (ref "U$5") (pin "4") (pinfunction "PVDDL1_4") (pintype "bidirectional"))
      (node (ref "U$5") (pin "9") (pinfunction "PVDDL2_9") (pintype "bidirectional"))
    )
    (net (code "3") (name "AGND") (class "Default")
      (node (ref "C29") (pin "1") (pinfunction "1_1") (pintype "passive"))
      (node (ref "R5") (pin "1") (pinfunction "1_1") (pintype "passive"))
      (node (ref "U$1") (pin "AGND") (pinfunction "AGND_AGND") (pintype "power_in"))
      (node (ref "U$2") (pin "P$3") (pinfunction "P$3_P$3") (pintype "bidirectional"))
      (node (ref "U$5") (pin "1") (pinfunction "LINN_1") (pintype "bidirectional"))
      (node (ref "U$5") (pin "12") (pinfunction "AGND_12") (pintype "bidirectional"))
      (node (ref "U$5") (pin "24") (pinfunction "RINN_24") (pintype "bidirectional"))
      (node (ref "U$5") (pin "EXP") (pinfunction "AGND_EXP") (pintype "bidirectional"))
      (node (ref "U$5") (pin "EXP@1") (pinfunction "AGND_EXP@1") (pintype "bidirectional"))
      (node (ref "U$5") (pin "EXP@10") (pinfunction "AGND_EXP@10") (pintype "bidirectional"))
      (node (ref "U$5") (pin "EXP@11") (pinfunction "AGND_EXP@11") (pintype "bidirectional"))
      (node (ref "U$5") (pin "EXP@12") (pinfunction "AGND_EXP@12") (pintype "bidirectional"))
      (node (ref "U$5") (pin "EXP@13") (pinfunction "AGND_EXP@13") (pintype "bidirectional"))
      (node (ref "U$5") (pin "EXP@14") (pinfunction "AGND_EXP@14") (pintype "bidirectional"))
      (node (ref "U$5") (pin "EXP@15") (pinfunction "AGND_EXP@15") (pintype "bidirectional"))
      (node (ref "U$5") (pin "EXP@16") (pinfunction "AGND_EXP@16") (pintype "bidirectional"))
      (node (ref "U$5") (pin "EXP@17") (pinfunction "AGND_EXP@17") (pintype "bidirectional"))
      (node (ref "U$5") (pin "EXP@18") (pinfunction "AGND_EXP@18") (pintype "bidirectional"))
      (node (ref "U$5") (pin "EXP@2") (pinfunction "AGND_EXP@2") (pintype "bidirectional"))
      (node (ref "U$5") (pin "EXP@3") (pinfunction "AGND_EXP@3") (pintype "bidirectional"))
      (node (ref "U$5") (pin "EXP@4") (pinfunction "AGND_EXP@4") (pintype "bidirectional"))
      (node (ref "U$5") (pin "EXP@5") (pinfunction "AGND_EXP@5") (pintype "bidirectional"))
      (node (ref "U$5") (pin "EXP@6") (pinfunction "AGND_EXP@6") (pintype "bidirectional"))
      (node (ref "U$5") (pin "EXP@7") (pinfunction "AGND_EXP@7") (pintype "bidirectional"))
      (node (ref "U$5") (pin "EXP@8") (pinfunction "AGND_EXP@8") (pintype "bidirectional"))
      (node (ref "U$5") (pin "EXP@9") (pinfunction "AGND_EXP@9") (pintype "bidirectional"))
      (node (ref "U$7") (pin "P$3") (pinfunction "P$3_P$3") (pintype "bidirectional"))
      (node (ref "U$8") (pin "AGND") (pinfunction "AGND_AGND") (pintype "bidirectional"))
    )
    (net (code "4") (name "AUDIO_LEFT+") (class "Default")
      (node (ref "J1") (pin "1") (pinfunction "1_1") (pintype "passive"))
      (node (ref "J2") (pin "1") (pinfunction "1_1") (pintype "passive"))
      (node (ref "J3") (pin "1") (pinfunction "1_1") (pintype "passive"))
      (node (ref "J4") (pin "1") (pinfunction "1_1") (pintype "passive"))
      (node (ref "J5") (pin "1") (pinfunction "1_1") (pintype "passive"))
      (node (ref "U$5") (pin "5") (pinfunction "LOUTP_5") (pintype "bidirectional"))
    )
    (net (code "5") (name "AUDIO_LEFT-") (class "Default")
      (node (ref "J10") (pin "1") (pinfunction "1_1") (pintype "passive"))
      (node (ref "J11") (pin "1") (pinfunction "1_1") (pintype "passive"))
      (node (ref "J6") (pin "1") (pinfunction "1_1") (pintype "passive"))
      (node (ref "J8") (pin "1") (pinfunction "1_1") (pintype "passive"))
      (node (ref "J9") (pin "1") (pinfunction "1_1") (pintype "passive"))
      (node (ref "U$5") (pin "8") (pinfunction "LOUTN_8") (pintype "bidirectional"))
    )
    (net (code "6") (name "AUDIO_RIGHT+") (class "Default")
      (node (ref "J1") (pin "3") (pinfunction "3_3") (pintype "passive"))
      (node (ref "J2") (pin "3") (pinfunction "3_3") (pintype "passive"))
      (node (ref "J3") (pin "3") (pinfunction "3_3") (pintype "passive"))
      (node (ref "J4") (pin "3") (pinfunction "3_3") (pintype "passive"))
      (node (ref "J5") (pin "3") (pinfunction "3_3") (pintype "passive"))
      (node (ref "U$5") (pin "20") (pinfunction "ROUTP_20") (pintype "bidirectional"))
    )
    (net (code "7") (name "AUDIO_RIGHT-") (class "Default")
      (node (ref "J10") (pin "3") (pinfunction "3_3") (pintype "passive"))
      (node (ref "J11") (pin "3") (pinfunction "3_3") (pintype "passive"))
      (node (ref "J6") (pin "3") (pinfunction "3_3") (pintype "passive"))
      (node (ref "J8") (pin "3") (pinfunction "3_3") (pintype "passive"))
      (node (ref "J9") (pin "3") (pinfunction "3_3") (pintype "passive"))
      (node (ref "U$5") (pin "17") (pinfunction "ROUTN_17") (pintype "bidirectional"))
    )
    (net (code "8") (name "BCLK") (class "Default")
      (node (ref "MEMS1") (pin "4") (pinfunction "BCLK_4") (pintype "input"))
      (node (ref "U$1") (pin "9") (pinfunction "9/RX2/PWM_9") (pintype "bidirectional"))
      (node (ref "U$8") (pin "I2S_SCLK") (pinfunction "BCLK_I2S_SCLK") (pintype "bidirectional"))
    )
    (net (code "9") (name "BUT1") (class "Default")
      (node (ref "DIN3") (pin "1") (pinfunction "1_1") (pintype "passive"))
      (node (ref "U$1") (pin "0") (pinfunction "0/RX1/T_0") (pintype "bidirectional"))
    )
    (net (code "10") (name "BUT2") (class "Default")
      (node (ref "DIN4") (pin "1") (pinfunction "1_1") (pintype "passive"))
      (node (ref "U$1") (pin "1") (pinfunction "1/TX1/T_1") (pintype "bidirectional"))
    )
    (net (code "11") (name "BUT3") (class "Default")
      (node (ref "S3") (pin "14") (pinfunction "14_14") (pintype "passive"))
      (node (ref "U$1") (pin "4") (pinfunction "4/CAN-RX/PWM_4") (pintype "bidirectional"))
    )
    (net (code "12") (name "BUT4") (class "Default")
      (node (ref "S3") (pin "13") (pinfunction "13_13") (pintype "passive"))
      (node (ref "U$1") (pin "6") (pinfunction "6/PWM_6") (pintype "bidirectional"))
    )
    (net (code "13") (name "BUT5") (class "Default")
      (node (ref "S3") (pin "12") (pinfunction "12_12") (pintype "passive"))
      (node (ref "U$1") (pin "15/A1") (pinfunction "15/A1/T_15/A1") (pintype "bidirectional"))
    )
    (net (code "14") (name "BUT6") (class "Default")
      (node (ref "S3") (pin "11") (pinfunction "11_11") (pintype "passive"))
      (node (ref "U$1") (pin "16/A2") (pinfunction "16/A2/T_16/A2") (pintype "bidirectional"))
    )
    (net (code "15") (name "BUT7") (class "Default")
      (node (ref "S3") (pin "10") (pinfunction "10_10") (pintype "passive"))
      (node (ref "U$1") (pin "20/A6") (pinfunction "20/A6/PWM_20/A6") (pintype "bidirectional"))
    )
    (net (code "16") (name "BUT8") (class "Default")
      (node (ref "S3") (pin "9") (pinfunction "9_9") (pintype "passive"))
      (node (ref "U$1") (pin "21/A7") (pinfunction "21/A7/PWM_21/A7") (pintype "bidirectional"))
    )
    (net (code "17") (name "BYPASS") (class "Default")
      (node (ref "C32") (pin "1") (pinfunction "1_1") (pintype "passive"))
      (node (ref "U$5") (pin "22") (pinfunction "BYPASS_22") (pintype "bidirectional"))
    )
    (net (code "18") (name "COSC") (class "Default")
      (node (ref "C29") (pin "2") (pinfunction "2_2") (pintype "passive"))
      (node (ref "U$5") (pin "10") (pinfunction "COSC_10") (pintype "bidirectional"))
    )
    (net (code "19") (name "DIN") (class "Default")
      (node (ref "DIN") (pin "1") (pinfunction "1_1") (pintype "passive"))
      (node (ref "U$1") (pin "22/A8") (pinfunction "22/A8/T/PWM_22/A8") (pintype "bidirectional"))
    )
    (net (code "20") (name "DOUT") (class "Default")
      (node (ref "DOUT") (pin "1") (pinfunction "1_1") (pintype "passive"))
      (node (ref "R2") (pin "2") (pinfunction "2_2") (pintype "passive"))
      (node (ref "U$1") (pin "13") (pinfunction "13/SCK/LED_13") (pintype "bidirectional"))
    )
    (net (code "21") (name "GND") (class "Default")
      (node (ref "BT4") (pin "GND@1") (pinfunction "-_GND@1") (pintype "power_in"))
      (node (ref "C10") (pin "2") (pinfunction "2_2") (pintype "passive"))
      (node (ref "C11") (pin "2") (pinfunction "2_2") (pintype "passive"))
      (node (ref "C12") (pin "-") (pinfunction "-_-") (pintype "passive"))
      (node (ref "C13") (pin "-") (pinfunction "-_-") (pintype "passive"))
      (node (ref "C27") (pin "2") (pinfunction "2_2") (pintype "passive"))
      (node (ref "C28") (pin "2") (pinfunction "2_2") (pintype "passive"))
      (node (ref "C3") (pin "2") (pinfunction "2_2") (pintype "passive"))
      (node (ref "C32") (pin "2") (pinfunction "2_2") (pintype "passive"))
      (node (ref "C33") (pin "2") (pinfunction "2_2") (pintype "passive"))
      (node (ref "C34") (pin "2") (pinfunction "2_2") (pintype "passive"))
      (node (ref "C4") (pin "2") (pinfunction "2_2") (pintype "passive"))
      (node (ref "C41") (pin "2") (pinfunction "2_2") (pintype "passive"))
      (node (ref "C42") (pin "2") (pinfunction "2_2") (pintype "passive"))
      (node (ref "C43") (pin "2") (pinfunction "2_2") (pintype "passive"))
      (node (ref "C44") (pin "2") (pinfunction "2_2") (pintype "passive"))
      (node (ref "C45") (pin "2") (pinfunction "2_2") (pintype "passive"))
      (node (ref "C46") (pin "2") (pinfunction "2_2") (pintype "passive"))
      (node (ref "C47") (pin "2") (pinfunction "2_2") (pintype "passive"))
      (node (ref "C48") (pin "2") (pinfunction "2_2") (pintype "passive"))
      (node (ref "C49") (pin "2") (pinfunction "2_2") (pintype "passive"))
      (node (ref "C5") (pin "2") (pinfunction "2_2") (pintype "passive"))
      (node (ref "C50") (pin "2") (pinfunction "2_2") (pintype "passive"))
      (node (ref "C51") (pin "2") (pinfunction "2_2") (pintype "passive"))
      (node (ref "C52") (pin "2") (pinfunction "2_2") (pintype "passive"))
      (node (ref "C55") (pin "2") (pinfunction "2_2") (pintype "passive"))
      (node (ref "C56") (pin "2") (pinfunction "2_2") (pintype "passive"))
      (node (ref "C57") (pin "2") (pinfunction "2_2") (pintype "passive"))
      (node (ref "C58") (pin "2") (pinfunction "2_2") (pintype "passive"))
      (node (ref "C59") (pin "2") (pinfunction "2_2") (pintype "passive"))
      (node (ref "C60") (pin "2") (pinfunction "2_2") (pintype "passive"))
      (node (ref "C61") (pin "2") (pinfunction "2_2") (pintype "passive"))
      (node (ref "C62") (pin "2") (pinfunction "2_2") (pintype "passive"))
      (node (ref "C63") (pin "2") (pinfunction "2_2") (pintype "passive"))
      (node (ref "C64") (pin "2") (pinfunction "2_2") (pintype "passive"))
      (node (ref "C65") (pin "2") (pinfunction "2_2") (pintype "passive"))
      (node (ref "C66") (pin "2") (pinfunction "2_2") (pintype "passive"))
      (node (ref "C67") (pin "2") (pinfunction "2_2") (pintype "passive"))
      (node (ref "C68") (pin "2") (pinfunction "2_2") (pintype "passive"))
      (node (ref "C69") (pin "2") (pinfunction "2_2") (pintype "passive"))
      (node (ref "C7") (pin "2") (pinfunction "2_2") (pintype "passive"))
      (node (ref "C70") (pin "2") (pinfunction "2_2") (pintype "passive"))
      (node (ref "C71") (pin "2") (pinfunction "2_2") (pintype "passive"))
      (node (ref "C8") (pin "2") (pinfunction "2_2") (pintype "passive"))
      (node (ref "C9") (pin "2") (pinfunction "2_2") (pintype "passive"))
      (node (ref "J7") (pin "6") (pinfunction "VSS_6") (pintype "passive"))
      (node (ref "J7") (pin "S1") (pinfunction "GND_S1") (pintype "passive"))
      (node (ref "J7") (pin "S2") (pinfunction "GND_S2") (pintype "passive"))
      (node (ref "J7") (pin "S3") (pinfunction "GND_S3") (pintype "passive"))
      (node (ref "J7") (pin "S5") (pinfunction "GND_S5") (pintype "passive"))
      (node (ref "LED25") (pin "3-GND") (pinfunction "GND_3-GND") (pintype "power_in"))
      (node (ref "LED26") (pin "3-GND") (pinfunction "GND_3-GND") (pintype "power_in"))
      (node (ref "LED27") (pin "3-GND") (pinfunction "GND_3-GND") (pintype "power_in"))
      (node (ref "LED28") (pin "3-GND") (pinfunction "GND_3-GND") (pintype "power_in"))
      (node (ref "LED29") (pin "3-GND") (pinfunction "GND_3-GND") (pintype "power_in"))
      (node (ref "LED30") (pin "3-GND") (pinfunction "GND_3-GND") (pintype "power_in"))
      (node (ref "LED31") (pin "3-GND") (pinfunction "GND_3-GND") (pintype "power_in"))
      (node (ref "LED32") (pin "3-GND") (pinfunction "GND_3-GND") (pintype "power_in"))
      (node (ref "LED33") (pin "3-GND") (pinfunction "GND_3-GND") (pintype "power_in"))
      (node (ref "LED34") (pin "3-GND") (pinfunction "GND_3-GND") (pintype "power_in"))
      (node (ref "LED35") (pin "3-GND") (pinfunction "GND_3-GND") (pintype "power_in"))
      (node (ref "LED36") (pin "3-GND") (pinfunction "GND_3-GND") (pintype "power_in"))
      (node (ref "LED37") (pin "3-GND") (pinfunction "GND_3-GND") (pintype "power_in"))
      (node (ref "LED38") (pin "3-GND") (pinfunction "GND_3-GND") (pintype "power_in"))
      (node (ref "LED39") (pin "3-GND") (pinfunction "GND_3-GND") (pintype "power_in"))
      (node (ref "LED40") (pin "3-GND") (pinfunction "GND_3-GND") (pintype "power_in"))
      (node (ref "LED41") (pin "3-GND") (pinfunction "GND_3-GND") (pintype "power_in"))
      (node (ref "LED42") (pin "3-GND") (pinfunction "GND_3-GND") (pintype "power_in"))
      (node (ref "LED43") (pin "3-GND") (pinfunction "GND_3-GND") (pintype "power_in"))
      (node (ref "LED44") (pin "3-GND") (pinfunction "GND_3-GND") (pintype "power_in"))
      (node (ref "LED45") (pin "3-GND") (pinfunction "GND_3-GND") (pintype "power_in"))
      (node (ref "LED46") (pin "3-GND") (pinfunction "GND_3-GND") (pintype "power_in"))
      (node (ref "LED47") (pin "3-GND") (pinfunction "GND_3-GND") (pintype "power_in"))
      (node (ref "LED48") (pin "3-GND") (pinfunction "GND_3-GND") (pintype "power_in"))
      (node (ref "MEMS1") (pin "2") (pinfunction "SELECT_2") (pintype "input"))
      (node (ref "MEMS1") (pin "P$1") (pinfunction "GND_P$1") (pintype "power_in"))
      (node (ref "NEO_PIX2") (pin "3") (pinfunction "3_3") (pintype "passive"))
      (node (ref "PWR_REG1") (pin "GND") (pinfunction "GND_GND") (pintype "bidirectional"))
      (node (ref "S3") (pin "1") (pinfunction "1_1") (pintype "passive"))
      (node (ref "S3") (pin "2") (pinfunction "2_2") (pintype "passive"))
      (node (ref "S3") (pin "3") (pinfunction "3_3") (pintype "passive"))
      (node (ref "S3") (pin "4") (pinfunction "4_4") (pintype "passive"))
      (node (ref "S3") (pin "5") (pinfunction "5_5") (pintype "passive"))
      (node (ref "S3") (pin "6") (pinfunction "6_6") (pintype "passive"))
      (node (ref "S3") (pin "7") (pinfunction "7_7") (pintype "passive"))
      (node (ref "S3") (pin "8") (pinfunction "8_8") (pintype "passive"))
      (node (ref "S4") (pin "1") (pinfunction "O_1") (pintype "passive"))
      (node (ref "U$1") (pin "GND") (pinfunction "GND_GND") (pintype "power_in"))
      (node (ref "U$5") (pin "18") (pinfunction "PGNDR1_18") (pintype "bidirectional"))
      (node (ref "U$5") (pin "19") (pinfunction "PGNDR2_19") (pintype "bidirectional"))
      (node (ref "U$5") (pin "6") (pinfunction "PGNDL1_6") (pintype "bidirectional"))
      (node (ref "U$5") (pin "7") (pinfunction "PGNDL2_7") (pintype "bidirectional"))
      (node (ref "U$8") (pin "CTRL_ADR0_CS") (pinfunction "ADDR_CTRL_ADR0_CS") (pintype "bidirectional"))
      (node (ref "U$8") (pin "CTRL_MODE") (pinfunction "MODE_CTRL_MODE") (pintype "bidirectional"))
      (node (ref "U$8") (pin "GND1") (pinfunction "GND1_GND1") (pintype "bidirectional"))
      (node (ref "U$8") (pin "GND2") (pinfunction "GND2_GND2") (pintype "bidirectional"))
      (node (ref "U$8") (pin "GND3") (pinfunction "GND3_GND3") (pintype "bidirectional"))
      (node (ref "U$9") (pin "3") (pinfunction "GND_3") (pintype "bidirectional"))
      (node (ref "U2") (pin "4") (pinfunction "VSS_4") (pintype "bidirectional"))
      (node (ref "U2") (pin "5") (pinfunction "VSS_5") (pintype "bidirectional"))
      (node (ref "VEML1") (pin "3") (pinfunction "GND_3") (pintype "bidirectional"))
      (node (ref "VMEL1") (pin "1") (pinfunction "GND_1") (pintype "power_in"))
      (node (ref "VMEL1") (pin "4") (pinfunction "ADDR_4") (pintype "bidirectional"))
    )
    (net (code "22") (name "LOUT_L") (class "Default")
      (node (ref "C53") (pin "2") (pinfunction "2_2") (pintype "passive"))
      (node (ref "U$5") (pin "2") (pinfunction "LINP_2") (pintype "bidirectional"))
    )
    (net (code "23") (name "LOUT_R") (class "Default")
      (node (ref "C54") (pin "2") (pinfunction "2_2") (pintype "passive"))
      (node (ref "U$5") (pin "23") (pinfunction "RINP_23") (pintype "bidirectional"))
    )
    (net (code "24") (name "LRCLK") (class "Default")
      (node (ref "MEMS1") (pin "1") (pinfunction "WS_1") (pintype "input"))
      (node (ref "U$1") (pin "23/A9") (pinfunction "23/A9/T/PWM_23/A9") (pintype "bidirectional"))
      (node (ref "U$8") (pin "I2S_LRCLK") (pinfunction "LRCLK_I2S_LRCLK") (pintype "bidirectional"))
    )
    (net (code "25") (name "MCLK") (class "Default")
      (node (ref "R9") (pin "1") (pinfunction "1_1") (pintype "passive"))
      (node (ref "U$1") (pin "11") (pinfunction "11/MOSI_11") (pintype "bidirectional"))
    )
    (net (code "26") (name "MISO") (class "Default")
      (node (ref "J7") (pin "7") (pinfunction "DAT0_7") (pintype "passive"))
      (node (ref "U$1") (pin "12") (pinfunction "12/MISO_12") (pintype "bidirectional"))
    )
    (net (code "27") (name "MOSI") (class "Default")
      (node (ref "J7") (pin "3") (pinfunction "CMD_3") (pintype "passive"))
      (node (ref "U$1") (pin "7") (pinfunction "7/RX3_7") (pintype "bidirectional"))
    )
    (net (code "28") (name "NEO_PIX1") (class "Default")
      (node (ref "LED25") (pin "4-DIN") (pinfunction "DI_4-DIN") (pintype "input"))
      (node (ref "U$1") (pin "5") (pinfunction "5/PWM_5") (pintype "bidirectional"))
    )
    (net (code "29") (name "NEO_PIX1_OUT") (class "Default")
      (node (ref "LED40") (pin "2-DOUT") (pinfunction "DO_2-DOUT") (pintype "output"))
      (node (ref "LED41") (pin "4-DIN") (pinfunction "DI_4-DIN") (pintype "input"))
    )
    (net (code "30") (name "NEO_PIX2") (class "Default")
      (node (ref "NEO_PIX2") (pin "2") (pinfunction "2_2") (pintype "passive"))
      (node (ref "U$1") (pin "8") (pinfunction "8/TX3_8") (pintype "bidirectional"))
    )
    (net (code "31") (name "Net-(BT3--)") (class "Default")
      (node (ref "BT3") (pin "GND@1") (pinfunction "-_GND@1") (pintype "power_in"))
      (node (ref "BT4") (pin "PWR@1") (pinfunction "+_PWR@1") (pintype "power_in"))
    )
    (net (code "32") (name "Net-(C48-Pad1)") (class "Default")
      (node (ref "C48") (pin "1") (pinfunction "1_1") (pintype "passive"))
      (node (ref "C49") (pin "1") (pinfunction "1_1") (pintype "passive"))
      (node (ref "FERRITE1") (pin "2") (pinfunction "2_2") (pintype "passive"))
      (node (ref "U$8") (pin "VDDD") (pinfunction "VDDD_VDDD") (pintype "bidirectional"))
      (node (ref "U$8") (pin "VDDIO") (pinfunction "VDDIO_VDDIO") (pintype "bidirectional"))
    )
    (net (code "33") (name "Net-(C57-Pad1)") (class "Default")
      (node (ref "C57") (pin "1") (pinfunction "1_1") (pintype "passive"))
      (node (ref "U$8") (pin "VAG") (pinfunction "VAG_VAG") (pintype "bidirectional"))
    )
    (net (code "34") (name "Net-(J1-Pad2)") (class "Default")
      (node (ref "J1") (pin "2") (pinfunction "2_2") (pintype "passive"))
      (node (ref "MIC1") (pin "1") (pinfunction "1_1") (pintype "passive"))
    )
    (net (code "35") (name "Net-(J2-Pad2)") (class "Default")
      (node (ref "J2") (pin "2") (pinfunction "2_2") (pintype "passive"))
      (node (ref "MIC2") (pin "1") (pinfunction "1_1") (pintype "passive"))
    )
    (net (code "36") (name "Net-(J3-Pad2)") (class "Default")
      (node (ref "J3") (pin "2") (pinfunction "2_2") (pintype "passive"))
      (node (ref "MIC3") (pin "1") (pinfunction "1_1") (pintype "passive"))
    )
    (net (code "37") (name "Net-(J4-Pad2)") (class "Default")
      (node (ref "J4") (pin "2") (pinfunction "2_2") (pintype "passive"))
      (node (ref "MIC4") (pin "1") (pinfunction "1_1") (pintype "passive"))
    )
    (net (code "38") (name "Net-(J5-Pad2)") (class "Default")
      (node (ref "J5") (pin "2") (pinfunction "2_2") (pintype "passive"))
      (node (ref "MIC5") (pin "1") (pinfunction "1_1") (pintype "passive"))
    )
    (net (code "39") (name "Net-(J6-Pad2)") (class "Default")
      (node (ref "J6") (pin "2") (pinfunction "2_2") (pintype "passive"))
      (node (ref "MIC1") (pin "2") (pinfunction "2_2") (pintype "passive"))
    )
    (net (code "40") (name "Net-(J8-Pad2)") (class "Default")
      (node (ref "J8") (pin "2") (pinfunction "2_2") (pintype "passive"))
      (node (ref "MIC2") (pin "2") (pinfunction "2_2") (pintype "passive"))
    )
    (net (code "41") (name "Net-(J9-Pad2)") (class "Default")
      (node (ref "J9") (pin "2") (pinfunction "2_2") (pintype "passive"))
      (node (ref "MIC3") (pin "2") (pinfunction "2_2") (pintype "passive"))
    )
    (net (code "42") (name "Net-(J10-Pad2)") (class "Default")
      (node (ref "J10") (pin "2") (pinfunction "2_2") (pintype "passive"))
      (node (ref "MIC4") (pin "2") (pinfunction "2_2") (pintype "passive"))
    )
    (net (code "43") (name "Net-(J11-Pad2)") (class "Default")
      (node (ref "J11") (pin "2") (pinfunction "2_2") (pintype "passive"))
      (node (ref "MIC5") (pin "2") (pinfunction "2_2") (pintype "passive"))
    )
    (net (code "44") (name "Net-(LED25-DO)") (class "Default")
      (node (ref "LED25") (pin "2-DOUT") (pinfunction "DO_2-DOUT") (pintype "output"))
      (node (ref "LED26") (pin "4-DIN") (pinfunction "DI_4-DIN") (pintype "input"))
    )
    (net (code "45") (name "Net-(LED26-DO)") (class "Default")
      (node (ref "LED26") (pin "2-DOUT") (pinfunction "DO_2-DOUT") (pintype "output"))
      (node (ref "LED27") (pin "4-DIN") (pinfunction "DI_4-DIN") (pintype "input"))
    )
    (net (code "46") (name "Net-(LED27-DO)") (class "Default")
      (node (ref "LED27") (pin "2-DOUT") (pinfunction "DO_2-DOUT") (pintype "output"))
      (node (ref "LED28") (pin "4-DIN") (pinfunction "DI_4-DIN") (pintype "input"))
    )
    (net (code "47") (name "Net-(LED28-DO)") (class "Default")
      (node (ref "LED28") (pin "2-DOUT") (pinfunction "DO_2-DOUT") (pintype "output"))
      (node (ref "LED29") (pin "4-DIN") (pinfunction "DI_4-DIN") (pintype "input"))
    )
    (net (code "48") (name "Net-(LED29-DO)") (class "Default")
      (node (ref "LED29") (pin "2-DOUT") (pinfunction "DO_2-DOUT") (pintype "output"))
      (node (ref "LED30") (pin "4-DIN") (pinfunction "DI_4-DIN") (pintype "input"))
    )
    (net (code "49") (name "Net-(LED30-DO)") (class "Default")
      (node (ref "LED30") (pin "2-DOUT") (pinfunction "DO_2-DOUT") (pintype "output"))
      (node (ref "LED31") (pin "4-DIN") (pinfunction "DI_4-DIN") (pintype "input"))
    )
    (net (code "50") (name "Net-(LED31-DO)") (class "Default")
      (node (ref "LED31") (pin "2-DOUT") (pinfunction "DO_2-DOUT") (pintype "output"))
      (node (ref "LED32") (pin "4-DIN") (pinfunction "DI_4-DIN") (pintype "input"))
    )
    (net (code "51") (name "Net-(LED32-DO)") (class "Default")
      (node (ref "LED32") (pin "2-DOUT") (pinfunction "DO_2-DOUT") (pintype "output"))
      (node (ref "LED33") (pin "4-DIN") (pinfunction "DI_4-DIN") (pintype "input"))
    )
    (net (code "52") (name "Net-(LED33-DO)") (class "Default")
      (node (ref "LED33") (pin "2-DOUT") (pinfunction "DO_2-DOUT") (pintype "output"))
      (node (ref "LED34") (pin "4-DIN") (pinfunction "DI_4-DIN") (pintype "input"))
    )
    (net (code "53") (name "Net-(LED34-DO)") (class "Default")
      (node (ref "LED34") (pin "2-DOUT") (pinfunction "DO_2-DOUT") (pintype "output"))
      (node (ref "LED35") (pin "4-DIN") (pinfunction "DI_4-DIN") (pintype "input"))
    )
    (net (code "54") (name "Net-(LED35-DO)") (class "Default")
      (node (ref "LED35") (pin "2-DOUT") (pinfunction "DO_2-DOUT") (pintype "output"))
      (node (ref "LED36") (pin "4-DIN") (pinfunction "DI_4-DIN") (pintype "input"))
    )
    (net (code "55") (name "Net-(LED36-DO)") (class "Default")
      (node (ref "LED36") (pin "2-DOUT") (pinfunction "DO_2-DOUT") (pintype "output"))
      (node (ref "LED37") (pin "4-DIN") (pinfunction "DI_4-DIN") (pintype "input"))
    )
    (net (code "56") (name "Net-(LED37-DO)") (class "Default")
      (node (ref "LED37") (pin "2-DOUT") (pinfunction "DO_2-DOUT") (pintype "output"))
      (node (ref "LED38") (pin "4-DIN") (pinfunction "DI_4-DIN") (pintype "input"))
    )
    (net (code "57") (name "Net-(LED38-DO)") (class "Default")
      (node (ref "LED38") (pin "2-DOUT") (pinfunction "DO_2-DOUT") (pintype "output"))
      (node (ref "LED39") (pin "4-DIN") (pinfunction "DI_4-DIN") (pintype "input"))
    )
    (net (code "58") (name "Net-(LED39-DO)") (class "Default")
      (node (ref "LED39") (pin "2-DOUT") (pinfunction "DO_2-DOUT") (pintype "output"))
      (node (ref "LED40") (pin "4-DIN") (pinfunction "DI_4-DIN") (pintype "input"))
    )
    (net (code "59") (name "Net-(LED41-DO)") (class "Default")
      (node (ref "LED41") (pin "2-DOUT") (pinfunction "DO_2-DOUT") (pintype "output"))
      (node (ref "LED42") (pin "4-DIN") (pinfunction "DI_4-DIN") (pintype "input"))
    )
    (net (code "60") (name "Net-(LED42-DO)") (class "Default")
      (node (ref "LED42") (pin "2-DOUT") (pinfunction "DO_2-DOUT") (pintype "output"))
      (node (ref "LED43") (pin "4-DIN") (pinfunction "DI_4-DIN") (pintype "input"))
    )
    (net (code "61") (name "Net-(LED43-DO)") (class "Default")
      (node (ref "LED43") (pin "2-DOUT") (pinfunction "DO_2-DOUT") (pintype "output"))
      (node (ref "LED44") (pin "4-DIN") (pinfunction "DI_4-DIN") (pintype "input"))
    )
    (net (code "62") (name "Net-(LED44-DO)") (class "Default")
      (node (ref "LED44") (pin "2-DOUT") (pinfunction "DO_2-DOUT") (pintype "output"))
      (node (ref "LED45") (pin "4-DIN") (pinfunction "DI_4-DIN") (pintype "input"))
    )
    (net (code "63") (name "Net-(LED45-DO)") (class "Default")
      (node (ref "LED45") (pin "2-DOUT") (pinfunction "DO_2-DOUT") (pintype "output"))
      (node (ref "LED46") (pin "4-DIN") (pinfunction "DI_4-DIN") (pintype "input"))
    )
    (net (code "64") (name "Net-(LED46-DO)") (class "Default")
      (node (ref "LED46") (pin "2-DOUT") (pinfunction "DO_2-DOUT") (pintype "output"))
      (node (ref "LED47") (pin "4-DIN") (pinfunction "DI_4-DIN") (pintype "input"))
    )
    (net (code "65") (name "Net-(LED47-DO)") (class "Default")
      (node (ref "LED47") (pin "2-DOUT") (pinfunction "DO_2-DOUT") (pintype "output"))
      (node (ref "LED48") (pin "4-DIN") (pinfunction "DI_4-DIN") (pintype "input"))
    )
    (net (code "66") (name "Net-(MEMS1-DATA_OUT)") (class "Default")
      (node (ref "MEMS1") (pin "6") (pinfunction "DATA_OUT_6") (pintype "output"))
      (node (ref "R2") (pin "1") (pinfunction "1_1") (pintype "passive"))
    )
    (net (code "67") (name "Net-(S4-P)") (class "Default")
      (node (ref "PWR_REG1") (pin "EN") (pinfunction "EN_EN") (pintype "bidirectional"))
      (node (ref "S4") (pin "2") (pinfunction "P_2") (pintype "passive"))
    )
    (net (code "68") (name "Net-(U$8-LINEOUTL)") (class "Default")
      (node (ref "C54") (pin "1") (pinfunction "1_1") (pintype "passive"))
      (node (ref "U$8") (pin "LINEOUT_L") (pinfunction "LINEOUTL_LINEOUT_L") (pintype "bidirectional"))
    )
    (net (code "69") (name "Net-(U$8-LINEOUTR)") (class "Default")
      (node (ref "C53") (pin "1") (pinfunction "1_1") (pintype "passive"))
      (node (ref "U$8") (pin "LINEOUT_R") (pinfunction "LINEOUTR_LINEOUT_R") (pintype "bidirectional"))
    )
    (net (code "70") (name "Net-(U$8-MCLK)") (class "Default")
      (node (ref "R9") (pin "2") (pinfunction "2_2") (pintype "passive"))
      (node (ref "U$8") (pin "SYS_MCLK") (pinfunction "MCLK_SYS_MCLK") (pintype "bidirectional"))
    )
    (net (code "71") (name "Net-(U$8-RX)") (class "Default")
      (node (ref "DIN") (pin "2") (pinfunction "2_2") (pintype "passive"))
      (node (ref "U$8") (pin "I2S_DIN") (pinfunction "RX_I2S_DIN") (pintype "bidirectional"))
    )
    (net (code "72") (name "Net-(U$8-TX)") (class "Default")
      (node (ref "DOUT") (pin "2") (pinfunction "2_2") (pintype "passive"))
      (node (ref "U$8") (pin "I2S_DOUT") (pinfunction "TX_I2S_DOUT") (pintype "bidirectional"))
    )
    (net (code "73") (name "Net-(U$9-OUT)") (class "Default")
      (node (ref "C50") (pin "1") (pinfunction "1_1") (pintype "passive"))
      (node (ref "U$8") (pin "VDDA") (pinfunction "VDDA_VDDA") (pintype "bidirectional"))
      (node (ref "U$9") (pin "2") (pinfunction "OUT_2") (pintype "bidirectional"))
    )
    (net (code "74") (name "Net-(VEML1-VDD)") (class "Default")
      (node (ref "C10") (pin "1") (pinfunction "1_1") (pintype "passive"))
      (node (ref "C8") (pin "1") (pinfunction "1_1") (pintype "passive"))
      (node (ref "R1") (pin "1") (pinfunction "1_1") (pintype "passive"))
      (node (ref "VEML1") (pin "2") (pinfunction "VDD_2") (pintype "bidirectional"))
      (node (ref "VMEL1") (pin "6") (pinfunction "VDD_6") (pintype "power_in"))
    )
    (net (code "75") (name "POT1") (class "Default")
      (node (ref "U$1") (pin "17/A3") (pinfunction "17/A3/T_17/A3") (pintype "bidirectional"))
      (node (ref "U$2") (pin "P$1") (pinfunction "P$1_P$1") (pintype "bidirectional"))
    )
    (net (code "76") (name "ROSC") (class "Default")
      (node (ref "R5") (pin "2") (pinfunction "2_2") (pintype "passive"))
      (node (ref "U$5") (pin "11") (pinfunction "ROSC_11") (pintype "bidirectional"))
    )
    (net (code "77") (name "SCL") (class "Default")
      (node (ref "R4") (pin "1") (pinfunction "1_1") (pintype "passive"))
      (node (ref "U$1") (pin "19/A5") (pinfunction "19/A5/T/SCL0_19/A5") (pintype "bidirectional"))
      (node (ref "U$8") (pin "CTRL_CLK") (pinfunction "SCL_CTRL_CLK") (pintype "bidirectional"))
      (node (ref "U2") (pin "2") (pinfunction "SCL_2") (pintype "bidirectional"))
      (node (ref "VEML1") (pin "1") (pinfunction "SCL_1") (pintype "bidirectional"))
      (node (ref "VMEL1") (pin "5") (pinfunction "SCL_5") (pintype "input"))
    )
    (net (code "78") (name "SDA") (class "Default")
      (node (ref "R3") (pin "1") (pinfunction "1_1") (pintype "passive"))
      (node (ref "U$1") (pin "18/A4") (pinfunction "18/A4/T/SDA0_18/A4") (pintype "bidirectional"))
      (node (ref "U$8") (pin "CTRL_DATA") (pinfunction "SDA_CTRL_DATA") (pintype "bidirectional"))
      (node (ref "U2") (pin "3") (pinfunction "SDA_3") (pintype "bidirectional"))
      (node (ref "VEML1") (pin "4") (pinfunction "SDA_4") (pintype "bidirectional"))
      (node (ref "VMEL1") (pin "2") (pinfunction "SDA_2") (pintype "bidirectional"))
    )
    (net (code "79") (name "SD_CS") (class "Default")
      (node (ref "J7") (pin "2") (pinfunction "CD/DAT3_2") (pintype "passive"))
      (node (ref "R11") (pin "1") (pinfunction "1_1") (pintype "passive"))
      (node (ref "U$1") (pin "10") (pinfunction "10/TX2/PWM_10") (pintype "bidirectional"))
    )
    (net (code "80") (name "SPI_CLK") (class "Default")
      (node (ref "J7") (pin "5") (pinfunction "CLK_5") (pintype "passive"))
      (node (ref "U$1") (pin "14/A0") (pinfunction "14/A1_14/A0") (pintype "bidirectional"))
    )
    (net (code "81") (name "TPA_SHDN") (class "Default")
      (node (ref "U$1") (pin "3") (pinfunction "3/CAN-TX/PWM_3") (pintype "bidirectional"))
      (node (ref "U$5") (pin "3") (pinfunction "SHDN_3") (pintype "bidirectional"))
    )
    (net (code "82") (name "VEML_INT") (class "Default")
      (node (ref "U$1") (pin "2") (pinfunction "2_2") (pintype "bidirectional"))
      (node (ref "VMEL1") (pin "3") (pinfunction "INT_3") (pintype "output"))
    )
    (net (code "83") (name "VIN") (class "Default")
      (node (ref "BT3") (pin "PWR@1") (pinfunction "+_PWR@1") (pintype "power_in"))
      (node (ref "C12") (pin "+") (pinfunction "+_+") (pintype "passive"))
      (node (ref "PWR_REG1") (pin "VIN") (pinfunction "VIN_VIN") (pintype "bidirectional"))
    )
    (net (code "84") (name "VOL") (class "Default")
      (node (ref "U$5") (pin "14") (pinfunction "VOL_14") (pintype "bidirectional"))
      (node (ref "U$7") (pin "P$1") (pinfunction "P$1_P$1") (pintype "bidirectional"))
    )
    (net (code "85") (name "_BUT1") (class "Default")
      (node (ref "DIN3") (pin "2") (pinfunction "2_2") (pintype "passive"))
      (node (ref "S3") (pin "16") (pinfunction "16_16") (pintype "passive"))
    )
    (net (code "86") (name "_BUT2") (class "Default")
      (node (ref "DIN4") (pin "2") (pinfunction "2_2") (pintype "passive"))
      (node (ref "S3") (pin "15") (pinfunction "15_15") (pintype "passive"))
    )
    (net (code "87") (name "unconnected-(J7-CD_SW-Pad9)") (class "Default")
      (node (ref "J7") (pin "9") (pinfunction "CD_SW_9") (pintype "passive"))
    )
    (net (code "88") (name "unconnected-(J7-DAT1-Pad8)") (class "Default")
      (node (ref "J7") (pin "8") (pinfunction "DAT1_8") (pintype "passive"))
    )
    (net (code "89") (name "unconnected-(J7-DAT2-Pad1)") (class "Default")
      (node (ref "J7") (pin "1") (pinfunction "DAT2_1") (pintype "passive"))
    )
    (net (code "90") (name "unconnected-(LED48-DO-Pad2-DOUT)") (class "Default")
      (node (ref "LED48") (pin "2-DOUT") (pinfunction "DO_2-DOUT") (pintype "output"))
    )
    (net (code "91") (name "unconnected-(PWR_REG1-PadPG)") (class "Default")
      (node (ref "PWR_REG1") (pin "PG") (pinfunction "PG_PG") (pintype "bidirectional"))
    )
    (net (code "92") (name "unconnected-(PWR_REG1-PadSEL)") (class "Default")
      (node (ref "PWR_REG1") (pin "SEL") (pinfunction "SEL_SEL") (pintype "bidirectional"))
    )
    (net (code "93") (name "unconnected-(S4-S-Pad3)") (class "Default")
      (node (ref "S4") (pin "3") (pinfunction "S_3") (pintype "passive"))
    )
    (net (code "94") (name "unconnected-(U$5-NC-Pad15)") (class "Default")
      (node (ref "U$5") (pin "15") (pinfunction "NC_15") (pintype "bidirectional"))
    )
    (net (code "95") (name "unconnected-(U$8-HPL-PadHP_L)") (class "Default")
      (node (ref "U$8") (pin "HP_L") (pinfunction "HPL_HP_L") (pintype "bidirectional"))
    )
    (net (code "96") (name "unconnected-(U$8-HPR-PadHP_R)") (class "Default")
      (node (ref "U$8") (pin "HP_R") (pinfunction "HPR_HP_R") (pintype "bidirectional"))
    )
    (net (code "97") (name "unconnected-(U$8-HPVGND-PadHP_VGND)") (class "Default")
      (node (ref "U$8") (pin "HP_VGND") (pinfunction "HPVGND_HP_VGND") (pintype "bidirectional"))
    )
    (net (code "98") (name "unconnected-(U$8-LINEINL-PadLININ_L)") (class "Default")
      (node (ref "U$8") (pin "LININ_L") (pinfunction "LINEINL_LININ_L") (pintype "bidirectional"))
    )
    (net (code "99") (name "unconnected-(U$8-LINEINR-PadLININ_R)") (class "Default")
      (node (ref "U$8") (pin "LININ_R") (pinfunction "LINEINR_LININ_R") (pintype "bidirectional"))
    )
    (net (code "100") (name "unconnected-(U$8-MICBIAS-PadMIC_BIAS)") (class "Default")
      (node (ref "U$8") (pin "MIC_BIAS") (pinfunction "MICBIAS_MIC_BIAS") (pintype "bidirectional"))
    )
    (net (code "101") (name "unconnected-(U$8-PadCPFILT)") (class "Default")
      (node (ref "U$8") (pin "CPFILT") (pinfunction "CPFILT_CPFILT") (pintype "bidirectional"))
    )
    (net (code "102") (name "unconnected-(U$8-PadMIC)") (class "Default")
      (node (ref "U$8") (pin "MIC") (pinfunction "MIC_MIC") (pintype "bidirectional"))
    )
  )
)
